# SparkFun_Micro_6DoF_LSM6DSV16X.net
KiCad netlist of a schematic drawn in EAGLE
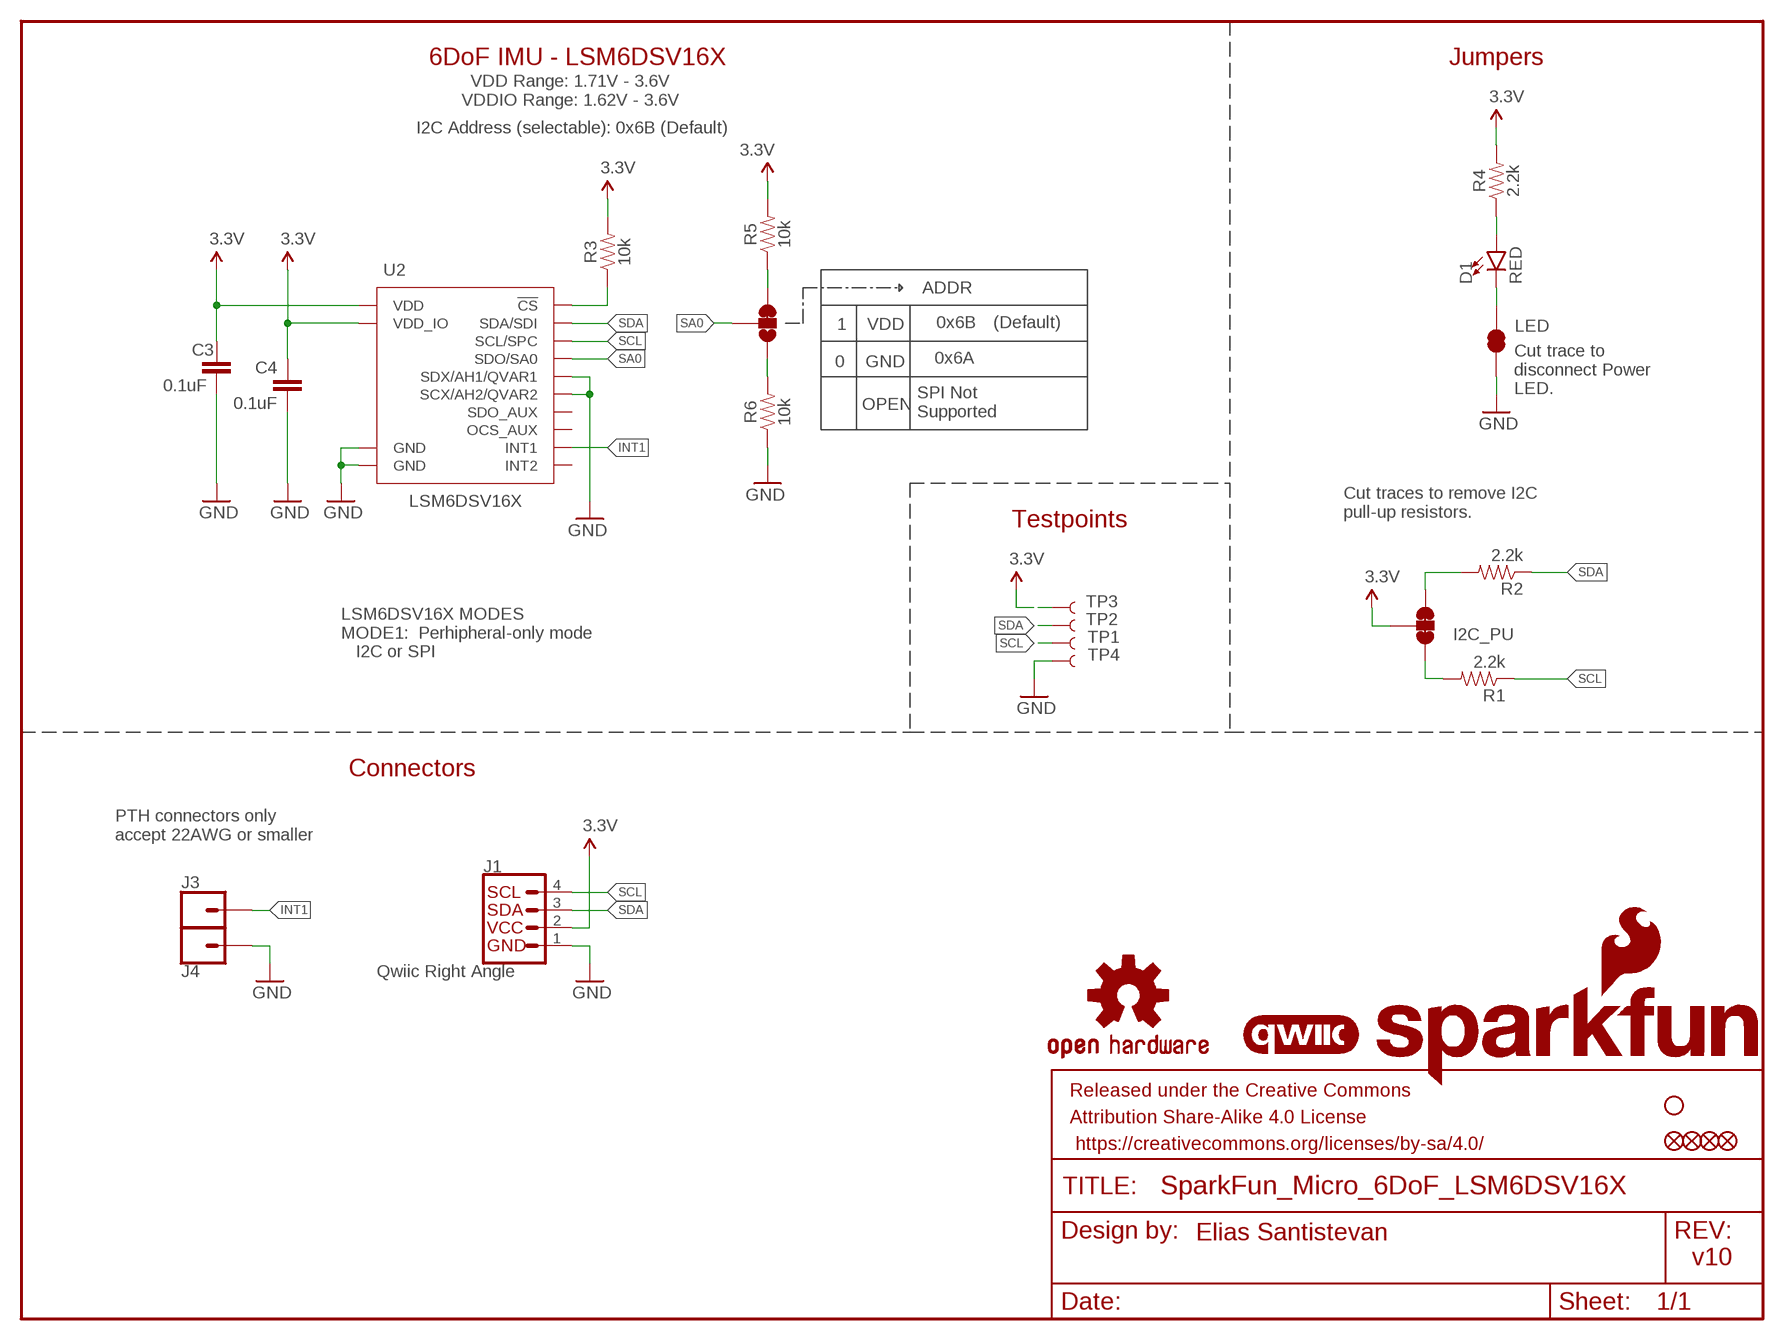
[diagram p0: schematic, sheet 1]

(export (version "E")
  (design (tool "Eeschema 10.0.6"))
  (components
    (comp (ref "ADDR")
      (value "JUMPER-SMT_3_1-NC_TRACE_SILK")
      (footprint "eagle-import:SMT-JUMPER_3_1-NC_TRACE_SILK")
      (libsource (lib "eagle-import") (part "JUMPER-SMT_3_1-NC_TRACE_SILK"))
    )
    (comp (ref "C3")
      (value "0.1uF")
      (footprint "eagle-import:0402-TIGHT")
      (libsource (lib "eagle-import") (part "0.1UF-0402T-6.3V-10%-X7R"))
    )
    (comp (ref "C4")
      (value "0.1uF")
      (footprint "eagle-import:0402-TIGHT")
      (libsource (lib "eagle-import") (part "0.1UF-0402T-6.3V-10%-X7R"))
    )
    (comp (ref "D1")
      (value "RED")
      (footprint "eagle-import:LED-0402")
      (libsource (lib "eagle-import") (part "LED-RED_0402"))
    )
    (comp (ref "FD1")
      (value "FIDUCIALUFIDUCIAL")
      (footprint "eagle-import:FIDUCIAL-MICRO")
      (libsource (lib "eagle-import") (part "FIDUCIALUFIDUCIAL"))
    )
    (comp (ref "FD2")
      (value "FIDUCIALUFIDUCIAL")
      (footprint "eagle-import:FIDUCIAL-MICRO")
      (libsource (lib "eagle-import") (part "FIDUCIALUFIDUCIAL"))
    )
    (comp (ref "FID1")
      (value "FIDUCIALUFIDUCIAL")
      (footprint "eagle-import:FIDUCIAL-MICRO")
      (libsource (lib "eagle-import") (part "FIDUCIALUFIDUCIAL"))
    )
    (comp (ref "FID2")
      (value "FIDUCIALUFIDUCIAL")
      (footprint "eagle-import:FIDUCIAL-MICRO")
      (libsource (lib "eagle-import") (part "FIDUCIALUFIDUCIAL"))
    )
    (comp (ref "FRAME1")
      (value "FRAME-LETTER")
      (footprint "eagle-import:CREATIVE_COMMONS")
      (fields (field (name "DESIGNER") "Elias Santistevan"))
      (libsource (lib "eagle-import") (part "FRAME-LETTER"))
    )
    (comp (ref "I2C_PU")
      (value "S_MODE")
      (footprint "eagle-import:SMT-JUMPER_3_2-NC_TRACE_SILK")
      (libsource (lib "eagle-import") (part "JUMPER-SMT_3_2-NC_TRACE_SILK"))
    )
    (comp (ref "J1")
      (value "Qwiic Right Angle")
      (footprint "eagle-import:JST04_1MM_RA")
      (libsource (lib "eagle-import") (part "I2C_STANDARDQWIIC"))
    )
    (comp (ref "J3")
      (value "CONN_01_1MM")
      (footprint "eagle-import:1X01_1MM_NO_SILK")
      (libsource (lib "eagle-import") (part "CONN_01_1MM"))
    )
    (comp (ref "J4")
      (value "CONN_01_1MM")
      (footprint "eagle-import:1X01_1MM_NO_SILK")
      (libsource (lib "eagle-import") (part "CONN_01_1MM"))
    )
    (comp (ref "LED")
      (value "JUMPER-SMT_2_NC_TRACE_SILK")
      (footprint "eagle-import:SMT-JUMPER_2_NC_TRACE_SILK")
      (libsource (lib "eagle-import") (part "JUMPER-SMT_2_NC_TRACE_SILK"))
    )
    (comp (ref "LOGO1")
      (value "QWIIC_LOGO_3MM")
      (footprint "eagle-import:QWIIC_3MM")
      (libsource (lib "eagle-import") (part "QWIIC_LOGO_3MM"))
    )
    (comp (ref "LOGO2")
      (value "OSHW-LOGOMINI")
      (footprint "eagle-import:OSHW-LOGO-MINI")
      (libsource (lib "eagle-import") (part "OSHW-LOGOMINI"))
    )
    (comp (ref "LOGO3")
      (value "SFE_LOGO_NAME_FLAMEBLANK")
      (footprint "eagle-import:BLANK")
      (libsource (lib "eagle-import") (part "SFE_LOGO_NAME_FLAMEBLANK"))
    )
    (comp (ref "R1")
      (value "2.2k")
      (footprint "eagle-import:0402-TIGHT")
      (libsource (lib "eagle-import") (part "2.2KOHM-0402T-1/16W-1%"))
    )
    (comp (ref "R2")
      (value "2.2k")
      (footprint "eagle-import:0402-TIGHT")
      (libsource (lib "eagle-import") (part "2.2KOHM-0402T-1/16W-1%"))
    )
    (comp (ref "R3")
      (value "10k")
      (footprint "eagle-import:0402-TIGHT")
      (libsource (lib "eagle-import") (part "10KOHM-0402T-1/16W-1%"))
    )
    (comp (ref "R4")
      (value "2.2k")
      (footprint "eagle-import:0402-TIGHT")
      (libsource (lib "eagle-import") (part "2.2KOHM-0402T-1/16W-1%"))
    )
    (comp (ref "R5")
      (value "10k")
      (footprint "eagle-import:0402-TIGHT")
      (libsource (lib "eagle-import") (part "10KOHM-0402T-1/16W-1%"))
    )
    (comp (ref "R6")
      (value "10k")
      (footprint "eagle-import:0402-TIGHT")
      (libsource (lib "eagle-import") (part "10KOHM-0402T-1/16W-1%"))
    )
    (comp (ref "STANDOFF1")
      (value "STAND-OFFTIGHT")
      (footprint "eagle-import:STAND-OFF-TIGHT")
      (libsource (lib "eagle-import") (part "STAND-OFFTIGHT"))
    )
    (comp (ref "TP1")
      (value "TEST-POINT3")
      (footprint "eagle-import:PAD.03X.03")
      (libsource (lib "eagle-import") (part "TEST-POINT3"))
    )
    (comp (ref "TP2")
      (value "TEST-POINT3")
      (footprint "eagle-import:PAD.03X.03")
      (libsource (lib "eagle-import") (part "TEST-POINT3"))
    )
    (comp (ref "TP3")
      (value "TEST-POINT3")
      (footprint "eagle-import:PAD.03X.03")
      (libsource (lib "eagle-import") (part "TEST-POINT3"))
    )
    (comp (ref "TP4")
      (value "TEST-POINT3")
      (footprint "eagle-import:PAD.03X.03")
      (libsource (lib "eagle-import") (part "TEST-POINT3"))
    )
    (comp (ref "U2")
      (value "LSM6DSV16X")
      (footprint "eagle-import:LGA-14L")
      (libsource (lib "eagle-import") (part "LSM6DSV16X"))
    )
  )
  (nets
    (net (code "1") (name "3.3V") (class "Default")
      (node (ref "C3") (pin "1") (pinfunction "1_1") (pintype "passive"))
      (node (ref "C4") (pin "1") (pinfunction "1_1") (pintype "passive"))
      (node (ref "I2C_PU") (pin "2") (pinfunction "2_2") (pintype "passive"))
      (node (ref "J1") (pin "2") (pinfunction "2_2") (pintype "power_in"))
      (node (ref "R3") (pin "2") (pinfunction "2_2") (pintype "passive"))
      (node (ref "R4") (pin "2") (pinfunction "2_2") (pintype "passive"))
      (node (ref "R5") (pin "2") (pinfunction "2_2") (pintype "passive"))
      (node (ref "TP3") (pin "1") (pinfunction "1_1") (pintype "bidirectional"))
      (node (ref "U2") (pin "P5") (pinfunction "VDD_IO_P5") (pintype "power_in"))
      (node (ref "U2") (pin "P8") (pinfunction "VDD_P8") (pintype "power_in"))
    )
    (net (code "2") (name "GND") (class "Default")
      (node (ref "C3") (pin "2") (pinfunction "2_2") (pintype "passive"))
      (node (ref "C4") (pin "2") (pinfunction "2_2") (pintype "passive"))
      (node (ref "J1") (pin "1") (pinfunction "1_1") (pintype "power_in"))
      (node (ref "J4") (pin "1") (pinfunction "1_1") (pintype "passive"))
      (node (ref "LED") (pin "1") (pinfunction "1_1") (pintype "passive"))
      (node (ref "R6") (pin "1") (pinfunction "1_1") (pintype "passive"))
      (node (ref "TP4") (pin "1") (pinfunction "1_1") (pintype "bidirectional"))
      (node (ref "U2") (pin "P2") (pinfunction "SDX/AH1/QVAR1_P2") (pintype "bidirectional"))
      (node (ref "U2") (pin "P3") (pinfunction "SCX/AH2/QVAR2_P3") (pintype "bidirectional"))
      (node (ref "U2") (pin "P6") (pinfunction "GND_P6") (pintype "power_in"))
      (node (ref "U2") (pin "P7") (pinfunction "GND_P7") (pintype "power_in"))
    )
    (net (code "3") (name "INT1") (class "Default")
      (node (ref "J3") (pin "1") (pinfunction "1_1") (pintype "passive"))
      (node (ref "U2") (pin "P4") (pinfunction "INT1_P4") (pintype "bidirectional"))
    )
    (net (code "4") (name "Net-(ADDR-Pad1)") (class "Default")
      (node (ref "ADDR") (pin "1") (pinfunction "1_1") (pintype "passive"))
      (node (ref "R6") (pin "2") (pinfunction "2_2") (pintype "passive"))
    )
    (net (code "5") (name "Net-(ADDR-Pad3)") (class "Default")
      (node (ref "ADDR") (pin "3") (pinfunction "3_3") (pintype "passive"))
      (node (ref "R5") (pin "1") (pinfunction "1_1") (pintype "passive"))
    )
    (net (code "6") (name "Net-(D1-PadA)") (class "Default")
      (node (ref "D1") (pin "A") (pinfunction "A_A") (pintype "passive"))
      (node (ref "R4") (pin "1") (pinfunction "1_1") (pintype "passive"))
    )
    (net (code "7") (name "Net-(D1-PadC)") (class "Default")
      (node (ref "D1") (pin "C") (pinfunction "C_C") (pintype "passive"))
      (node (ref "LED") (pin "2") (pinfunction "2_2") (pintype "passive"))
    )
    (net (code "8") (name "Net-(I2C_PU-Pad1)") (class "Default")
      (node (ref "I2C_PU") (pin "1") (pinfunction "1_1") (pintype "passive"))
      (node (ref "R1") (pin "2") (pinfunction "2_2") (pintype "passive"))
    )
    (net (code "9") (name "Net-(I2C_PU-Pad3)") (class "Default")
      (node (ref "I2C_PU") (pin "3") (pinfunction "3_3") (pintype "passive"))
      (node (ref "R2") (pin "2") (pinfunction "2_2") (pintype "passive"))
    )
    (net (code "10") (name "Net-(U2-~{CS})") (class "Default")
      (node (ref "R3") (pin "1") (pinfunction "1_1") (pintype "passive"))
      (node (ref "U2") (pin "P12") (pinfunction "~{CS}_P12") (pintype "bidirectional"))
    )
    (net (code "11") (name "SA0") (class "Default")
      (node (ref "ADDR") (pin "2") (pinfunction "2_2") (pintype "passive"))
      (node (ref "U2") (pin "P1") (pinfunction "SDO/SA0_P1") (pintype "bidirectional"))
    )
    (net (code "12") (name "SCL") (class "Default")
      (node (ref "J1") (pin "4") (pinfunction "4_4") (pintype "passive"))
      (node (ref "R1") (pin "1") (pinfunction "1_1") (pintype "passive"))
      (node (ref "TP1") (pin "1") (pinfunction "1_1") (pintype "bidirectional"))
      (node (ref "U2") (pin "P13") (pinfunction "SCL/SPC_P13") (pintype "bidirectional"))
    )
    (net (code "13") (name "SDA") (class "Default")
      (node (ref "J1") (pin "3") (pinfunction "3_3") (pintype "passive"))
      (node (ref "R2") (pin "1") (pinfunction "1_1") (pintype "passive"))
      (node (ref "TP2") (pin "1") (pinfunction "1_1") (pintype "bidirectional"))
      (node (ref "U2") (pin "P14") (pinfunction "SDA/SDI_P14") (pintype "bidirectional"))
    )
    (net (code "14") (name "unconnected-(U2-INT2-PadP9)") (class "Default")
      (node (ref "U2") (pin "P9") (pinfunction "INT2_P9") (pintype "bidirectional"))
    )
    (net (code "15") (name "unconnected-(U2-OCS_AUX-PadP10)") (class "Default")
      (node (ref "U2") (pin "P10") (pinfunction "OCS_AUX_P10") (pintype "bidirectional"))
    )
    (net (code "16") (name "unconnected-(U2-SDO_AUX-PadP11)") (class "Default")
      (node (ref "U2") (pin "P11") (pinfunction "SDO_AUX_P11") (pintype "bidirectional"))
    )
  )
)
